# HunterRemote2.net
KiCad netlist of a schematic drawn in EAGLE
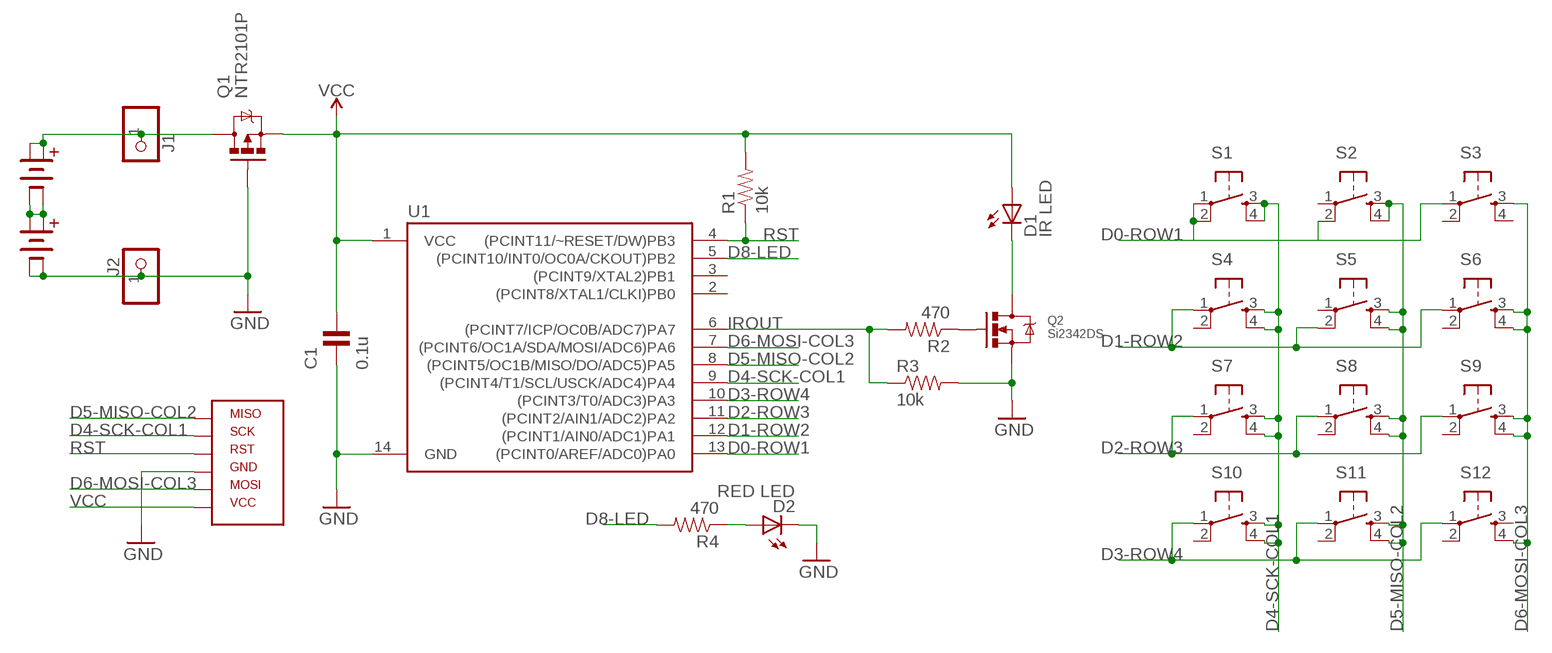
[diagram p0: schematic, sheet 1]

(export (version "E")
  (design (tool "Eeschema 10.0.6"))
  (components
    (comp (ref "B1")
      (value "BATTERYAAA-KEYSTONE-55TR")
      (footprint "eagle-import:KEYSTONE_55TR_AAA")
      (libsource (lib "eagle-import") (part "BATTERYAAA-KEYSTONE-55TR"))
    )
    (comp (ref "B2")
      (value "BATTERYAAA-KEYSTONE-55TR")
      (footprint "eagle-import:KEYSTONE_55TR_AAA")
      (libsource (lib "eagle-import") (part "BATTERYAAA-KEYSTONE-55TR"))
    )
    (comp (ref "C1")
      (value "0.1u")
      (footprint "eagle-import:C0805")
      (libsource (lib "eagle-import") (part "CAPACITOR0805"))
    )
    (comp (ref "D1")
      (value "IR LED")
      (footprint "eagle-import:LED5MM-90")
      (libsource (lib "eagle-import") (part "LED5MM_RIGHTANGLE"))
    )
    (comp (ref "D2")
      (value "RED LED")
      (footprint "eagle-import:LED-0805-RED")
      (libsource (lib "eagle-import") (part "LED0805-RED"))
    )
    (comp (ref "J1")
      (value "PINHD-1X1")
      (footprint "eagle-import:1X01")
      (libsource (lib "eagle-import") (part "PINHD-1X1"))
    )
    (comp (ref "J2")
      (value "PINHD-1X1")
      (footprint "eagle-import:1X01")
      (libsource (lib "eagle-import") (part "PINHD-1X1"))
    )
    (comp (ref "Q1")
      (value "NTR2101P")
      (footprint "eagle-import:SOT23-3A")
      (libsource (lib "eagle-import") (part "MOSFET_P_CH"))
    )
    (comp (ref "Q2")
      (value "Si2342DS")
      (footprint "eagle-import:SOT23-3A")
      (libsource (lib "eagle-import") (part "MOSFET_N_CHSOT23-3"))
    )
    (comp (ref "R1")
      (value "10k")
      (footprint "eagle-import:R0805")
      (libsource (lib "eagle-import") (part "RESISTORR0805-SMD"))
    )
    (comp (ref "R2")
      (value "470")
      (footprint "eagle-import:R0805")
      (libsource (lib "eagle-import") (part "RESISTORR0805-SMD"))
    )
    (comp (ref "R3")
      (value "10k")
      (footprint "eagle-import:R0805")
      (libsource (lib "eagle-import") (part "RESISTORR0805-SMD"))
    )
    (comp (ref "R4")
      (value "470")
      (footprint "eagle-import:R0805")
      (libsource (lib "eagle-import") (part "RESISTORR0805-SMD"))
    )
    (comp (ref "S1")
      (value "TAC_SWITCHSMD_5X5_LOW")
      (footprint "eagle-import:TACTILE_SWITCH_SMD_5X5_LOW")
      (libsource (lib "eagle-import") (part "TAC_SWITCHSMD_5X5_LOW"))
    )
    (comp (ref "S2")
      (value "TAC_SWITCHSMD_5X5_LOW")
      (footprint "eagle-import:TACTILE_SWITCH_SMD_5X5_LOW")
      (libsource (lib "eagle-import") (part "TAC_SWITCHSMD_5X5_LOW"))
    )
    (comp (ref "S3")
      (value "TAC_SWITCHSMD_5X5_LOW")
      (footprint "eagle-import:TACTILE_SWITCH_SMD_5X5_LOW")
      (libsource (lib "eagle-import") (part "TAC_SWITCHSMD_5X5_LOW"))
    )
    (comp (ref "S4")
      (value "TAC_SWITCHSMD_5X5_LOW")
      (footprint "eagle-import:TACTILE_SWITCH_SMD_5X5_LOW")
      (libsource (lib "eagle-import") (part "TAC_SWITCHSMD_5X5_LOW"))
    )
    (comp (ref "S5")
      (value "TAC_SWITCHSMD_5X5_LOW")
      (footprint "eagle-import:TACTILE_SWITCH_SMD_5X5_LOW")
      (libsource (lib "eagle-import") (part "TAC_SWITCHSMD_5X5_LOW"))
    )
    (comp (ref "S6")
      (value "TAC_SWITCHSMD_5X5_LOW")
      (footprint "eagle-import:TACTILE_SWITCH_SMD_5X5_LOW")
      (libsource (lib "eagle-import") (part "TAC_SWITCHSMD_5X5_LOW"))
    )
    (comp (ref "S7")
      (value "TAC_SWITCHSMD_5X5_LOW")
      (footprint "eagle-import:TACTILE_SWITCH_SMD_5X5_LOW")
      (libsource (lib "eagle-import") (part "TAC_SWITCHSMD_5X5_LOW"))
    )
    (comp (ref "S8")
      (value "TAC_SWITCHSMD_5X5_LOW")
      (footprint "eagle-import:TACTILE_SWITCH_SMD_5X5_LOW")
      (libsource (lib "eagle-import") (part "TAC_SWITCHSMD_5X5_LOW"))
    )
    (comp (ref "S9")
      (value "TAC_SWITCHSMD_5X5_LOW")
      (footprint "eagle-import:TACTILE_SWITCH_SMD_5X5_LOW")
      (libsource (lib "eagle-import") (part "TAC_SWITCHSMD_5X5_LOW"))
    )
    (comp (ref "S10")
      (value "TAC_SWITCHSMD_5X5_LOW")
      (footprint "eagle-import:TACTILE_SWITCH_SMD_5X5_LOW")
      (libsource (lib "eagle-import") (part "TAC_SWITCHSMD_5X5_LOW"))
    )
    (comp (ref "S11")
      (value "TAC_SWITCHSMD_5X5_LOW")
      (footprint "eagle-import:TACTILE_SWITCH_SMD_5X5_LOW")
      (libsource (lib "eagle-import") (part "TAC_SWITCHSMD_5X5_LOW"))
    )
    (comp (ref "S12")
      (value "TAC_SWITCHSMD_5X5_LOW")
      (footprint "eagle-import:TACTILE_SWITCH_SMD_5X5_LOW")
      (libsource (lib "eagle-import") (part "TAC_SWITCHSMD_5X5_LOW"))
    )
    (comp (ref "U$1")
      (value "AVR_ICSP_6PSTRAIGHT")
      (footprint "eagle-import:AVR_ICSP_6P_SMD_V2")
      (libsource (lib "eagle-import") (part "AVR_ICSP_6PSTRAIGHT"))
    )
    (comp (ref "U1")
      (value "ATTINY84")
      (footprint "eagle-import:SO14")
      (libsource (lib "eagle-import") (part "ATTINY84"))
    )
  )
  (nets
    (net (code "1") (name "/D0-ROW1") (class "Default")
      (node (ref "S1") (pin "1") (pinfunction "1_1") (pintype "passive"))
      (node (ref "S1") (pin "2") (pinfunction "2_2") (pintype "passive"))
      (node (ref "S2") (pin "2") (pinfunction "2_2") (pintype "passive"))
      (node (ref "S3") (pin "1") (pinfunction "1_1") (pintype "passive"))
      (node (ref "U1") (pin "13") (pinfunction "(PCINT0/AREF/ADC0)PA0_13") (pintype "bidirectional"))
    )
    (net (code "2") (name "/D1-ROW2") (class "Default")
      (node (ref "S4") (pin "1") (pinfunction "1_1") (pintype "passive"))
      (node (ref "S5") (pin "2") (pinfunction "2_2") (pintype "passive"))
      (node (ref "S6") (pin "1") (pinfunction "1_1") (pintype "passive"))
      (node (ref "U1") (pin "12") (pinfunction "(PCINT1/AIN0/ADC1)PA1_12") (pintype "bidirectional"))
    )
    (net (code "3") (name "/D2-ROW3") (class "Default")
      (node (ref "S7") (pin "1") (pinfunction "1_1") (pintype "passive"))
      (node (ref "S8") (pin "1") (pinfunction "1_1") (pintype "passive"))
      (node (ref "S9") (pin "1") (pinfunction "1_1") (pintype "passive"))
      (node (ref "U1") (pin "11") (pinfunction "(PCINT2/AIN1/ADC2)PA2_11") (pintype "bidirectional"))
    )
    (net (code "4") (name "/D3-ROW4") (class "Default")
      (node (ref "S10") (pin "1") (pinfunction "1_1") (pintype "passive"))
      (node (ref "S11") (pin "1") (pinfunction "1_1") (pintype "passive"))
      (node (ref "S12") (pin "1") (pinfunction "1_1") (pintype "passive"))
      (node (ref "U1") (pin "10") (pinfunction "(PCINT3/T0/ADC3)PA3_10") (pintype "bidirectional"))
    )
    (net (code "5") (name "/D4-SCK-COL1") (class "Default")
      (node (ref "S1") (pin "3") (pinfunction "3_3") (pintype "passive"))
      (node (ref "S1") (pin "4") (pinfunction "4_4") (pintype "passive"))
      (node (ref "S10") (pin "3") (pinfunction "3_3") (pintype "passive"))
      (node (ref "S10") (pin "4") (pinfunction "4_4") (pintype "passive"))
      (node (ref "S4") (pin "3") (pinfunction "3_3") (pintype "passive"))
      (node (ref "S4") (pin "4") (pinfunction "4_4") (pintype "passive"))
      (node (ref "S7") (pin "3") (pinfunction "3_3") (pintype "passive"))
      (node (ref "S7") (pin "4") (pinfunction "4_4") (pintype "passive"))
      (node (ref "U$1") (pin "SCK") (pinfunction "P$SCK_SCK") (pintype "bidirectional"))
      (node (ref "U1") (pin "9") (pinfunction "(PCINT4/T1/SCL/USCK/ADC4)PA4_9") (pintype "bidirectional"))
    )
    (net (code "6") (name "/D5-MISO-COL2") (class "Default")
      (node (ref "S11") (pin "3") (pinfunction "3_3") (pintype "passive"))
      (node (ref "S11") (pin "4") (pinfunction "4_4") (pintype "passive"))
      (node (ref "S2") (pin "3") (pinfunction "3_3") (pintype "passive"))
      (node (ref "S2") (pin "4") (pinfunction "4_4") (pintype "passive"))
      (node (ref "S5") (pin "3") (pinfunction "3_3") (pintype "passive"))
      (node (ref "S5") (pin "4") (pinfunction "4_4") (pintype "passive"))
      (node (ref "S8") (pin "3") (pinfunction "3_3") (pintype "passive"))
      (node (ref "S8") (pin "4") (pinfunction "4_4") (pintype "passive"))
      (node (ref "U$1") (pin "MISO") (pinfunction "P$MISO_MISO") (pintype "bidirectional"))
      (node (ref "U1") (pin "8") (pinfunction "(PCINT5/OC1B/MISO/DO/ADC5)PA5_8") (pintype "bidirectional"))
    )
    (net (code "7") (name "/D6-MOSI-COL3") (class "Default")
      (node (ref "S12") (pin "4") (pinfunction "4_4") (pintype "passive"))
      (node (ref "S3") (pin "3") (pinfunction "3_3") (pintype "passive"))
      (node (ref "S6") (pin "3") (pinfunction "3_3") (pintype "passive"))
      (node (ref "S6") (pin "4") (pinfunction "4_4") (pintype "passive"))
      (node (ref "S9") (pin "3") (pinfunction "3_3") (pintype "passive"))
      (node (ref "S9") (pin "4") (pinfunction "4_4") (pintype "passive"))
      (node (ref "U$1") (pin "MOSI") (pinfunction "P$MOSI_MOSI") (pintype "bidirectional"))
      (node (ref "U1") (pin "7") (pinfunction "(PCINT6/OC1A/SDA/MOSI/ADC6)PA6_7") (pintype "bidirectional"))
    )
    (net (code "8") (name "/D8-LED") (class "Default")
      (node (ref "R4") (pin "2") (pinfunction "2_2") (pintype "passive"))
      (node (ref "U1") (pin "5") (pinfunction "(PCINT10/INT0/OC0A/CKOUT)PB2_5") (pintype "bidirectional"))
    )
    (net (code "9") (name "/IROUT") (class "Default")
      (node (ref "R2") (pin "2") (pinfunction "2_2") (pintype "passive"))
      (node (ref "R3") (pin "1") (pinfunction "1_1") (pintype "passive"))
      (node (ref "U1") (pin "6") (pinfunction "(PCINT7/ICP/OC0B/ADC7)PA7_6") (pintype "bidirectional"))
    )
    (net (code "10") (name "/RST") (class "Default")
      (node (ref "R1") (pin "1") (pinfunction "1_1") (pintype "passive"))
      (node (ref "U$1") (pin "RST") (pinfunction "P$RST_RST") (pintype "bidirectional"))
      (node (ref "U1") (pin "4") (pinfunction "(PCINT11/~{RESET/DW})PB3_4") (pintype "bidirectional"))
    )
    (net (code "11") (name "GND") (class "Default")
      (node (ref "B1") (pin "NEG1") (pinfunction "NEG1_NEG1") (pintype "power_in"))
      (node (ref "B1") (pin "NEG2") (pinfunction "NEG2_NEG2") (pintype "power_in"))
      (node (ref "C1") (pin "1") (pinfunction "1_1") (pintype "passive"))
      (node (ref "D2") (pin "C") (pinfunction "C_C") (pintype "passive"))
      (node (ref "J2") (pin "1") (pinfunction "1_1") (pintype "passive"))
      (node (ref "Q1") (pin "1") (pinfunction "G_1") (pintype "passive"))
      (node (ref "Q2") (pin "2") (pinfunction "S_2") (pintype "passive"))
      (node (ref "R3") (pin "2") (pinfunction "2_2") (pintype "passive"))
      (node (ref "U$1") (pin "GND") (pinfunction "P$GND_GND") (pintype "bidirectional"))
      (node (ref "U1") (pin "14") (pinfunction "GND_14") (pintype "bidirectional"))
    )
    (net (code "12") (name "Net-(B1-PadPOS1)") (class "Default")
      (node (ref "B1") (pin "POS1") (pinfunction "POS1_POS1") (pintype "power_in"))
      (node (ref "B1") (pin "POS2") (pinfunction "POS2_POS2") (pintype "power_in"))
      (node (ref "B2") (pin "NEG1") (pinfunction "NEG1_NEG1") (pintype "power_in"))
      (node (ref "B2") (pin "NEG2") (pinfunction "NEG2_NEG2") (pintype "power_in"))
    )
    (net (code "13") (name "Net-(D2-PadA)") (class "Default")
      (node (ref "D2") (pin "A") (pinfunction "A_A") (pintype "passive"))
      (node (ref "R4") (pin "1") (pinfunction "1_1") (pintype "passive"))
    )
    (net (code "14") (name "Net-(Q1-D)") (class "Default")
      (node (ref "B2") (pin "POS1") (pinfunction "POS1_POS1") (pintype "power_in"))
      (node (ref "B2") (pin "POS2") (pinfunction "POS2_POS2") (pintype "power_in"))
      (node (ref "J1") (pin "1") (pinfunction "1_1") (pintype "passive"))
      (node (ref "Q1") (pin "3") (pinfunction "D_3") (pintype "passive"))
    )
    (net (code "15") (name "Net-(Q2-D)") (class "Default")
      (node (ref "D1") (pin "C") (pinfunction "C_C") (pintype "passive"))
      (node (ref "Q2") (pin "3") (pinfunction "D_3") (pintype "passive"))
    )
    (net (code "16") (name "Net-(Q2-G)") (class "Default")
      (node (ref "Q2") (pin "1") (pinfunction "G_1") (pintype "passive"))
      (node (ref "R2") (pin "1") (pinfunction "1_1") (pintype "passive"))
    )
    (net (code "17") (name "VCC") (class "Default")
      (node (ref "C1") (pin "2") (pinfunction "2_2") (pintype "passive"))
      (node (ref "D1") (pin "A") (pinfunction "A_A") (pintype "passive"))
      (node (ref "Q1") (pin "2") (pinfunction "S_2") (pintype "passive"))
      (node (ref "R1") (pin "2") (pinfunction "2_2") (pintype "passive"))
      (node (ref "U$1") (pin "VCC") (pinfunction "P$VCC_VCC") (pintype "bidirectional"))
      (node (ref "U1") (pin "1") (pinfunction "VCC_1") (pintype "bidirectional"))
    )
    (net (code "18") (name "unconnected-(S2-Pad1)") (class "Default")
      (node (ref "S2") (pin "1") (pinfunction "1_1") (pintype "passive"))
    )
    (net (code "19") (name "unconnected-(S3-Pad2)") (class "Default")
      (node (ref "S3") (pin "2") (pinfunction "2_2") (pintype "passive"))
    )
    (net (code "20") (name "unconnected-(S3-Pad4)") (class "Default")
      (node (ref "S3") (pin "4") (pinfunction "4_4") (pintype "passive"))
    )
    (net (code "21") (name "unconnected-(S4-Pad2)") (class "Default")
      (node (ref "S4") (pin "2") (pinfunction "2_2") (pintype "passive"))
    )
    (net (code "22") (name "unconnected-(S5-Pad1)") (class "Default")
      (node (ref "S5") (pin "1") (pinfunction "1_1") (pintype "passive"))
    )
    (net (code "23") (name "unconnected-(S6-Pad2)") (class "Default")
      (node (ref "S6") (pin "2") (pinfunction "2_2") (pintype "passive"))
    )
    (net (code "24") (name "unconnected-(S7-Pad2)") (class "Default")
      (node (ref "S7") (pin "2") (pinfunction "2_2") (pintype "passive"))
    )
    (net (code "25") (name "unconnected-(S8-Pad2)") (class "Default")
      (node (ref "S8") (pin "2") (pinfunction "2_2") (pintype "passive"))
    )
    (net (code "26") (name "unconnected-(S9-Pad2)") (class "Default")
      (node (ref "S9") (pin "2") (pinfunction "2_2") (pintype "passive"))
    )
    (net (code "27") (name "unconnected-(S10-Pad2)") (class "Default")
      (node (ref "S10") (pin "2") (pinfunction "2_2") (pintype "passive"))
    )
    (net (code "28") (name "unconnected-(S11-Pad2)") (class "Default")
      (node (ref "S11") (pin "2") (pinfunction "2_2") (pintype "passive"))
    )
    (net (code "29") (name "unconnected-(S12-Pad2)") (class "Default")
      (node (ref "S12") (pin "2") (pinfunction "2_2") (pintype "passive"))
    )
    (net (code "30") (name "unconnected-(S12-Pad3)") (class "Default")
      (node (ref "S12") (pin "3") (pinfunction "3_3") (pintype "passive"))
    )
    (net (code "31") (name "unconnected-(U1-(PCINT8{slash}XTAL1{slash}CLKI)PB0-Pad2)") (class "Default")
      (node (ref "U1") (pin "2") (pinfunction "(PCINT8/XTAL1/CLKI)PB0_2") (pintype "bidirectional"))
    )
    (net (code "32") (name "unconnected-(U1-(PCINT9{slash}XTAL2)PB1-Pad3)") (class "Default")
      (node (ref "U1") (pin "3") (pinfunction "(PCINT9/XTAL2)PB1_3") (pintype "bidirectional"))
    )
  )
)
